# Power_Management.net
KiCad netlist of a schematic drawn in Altium Designer
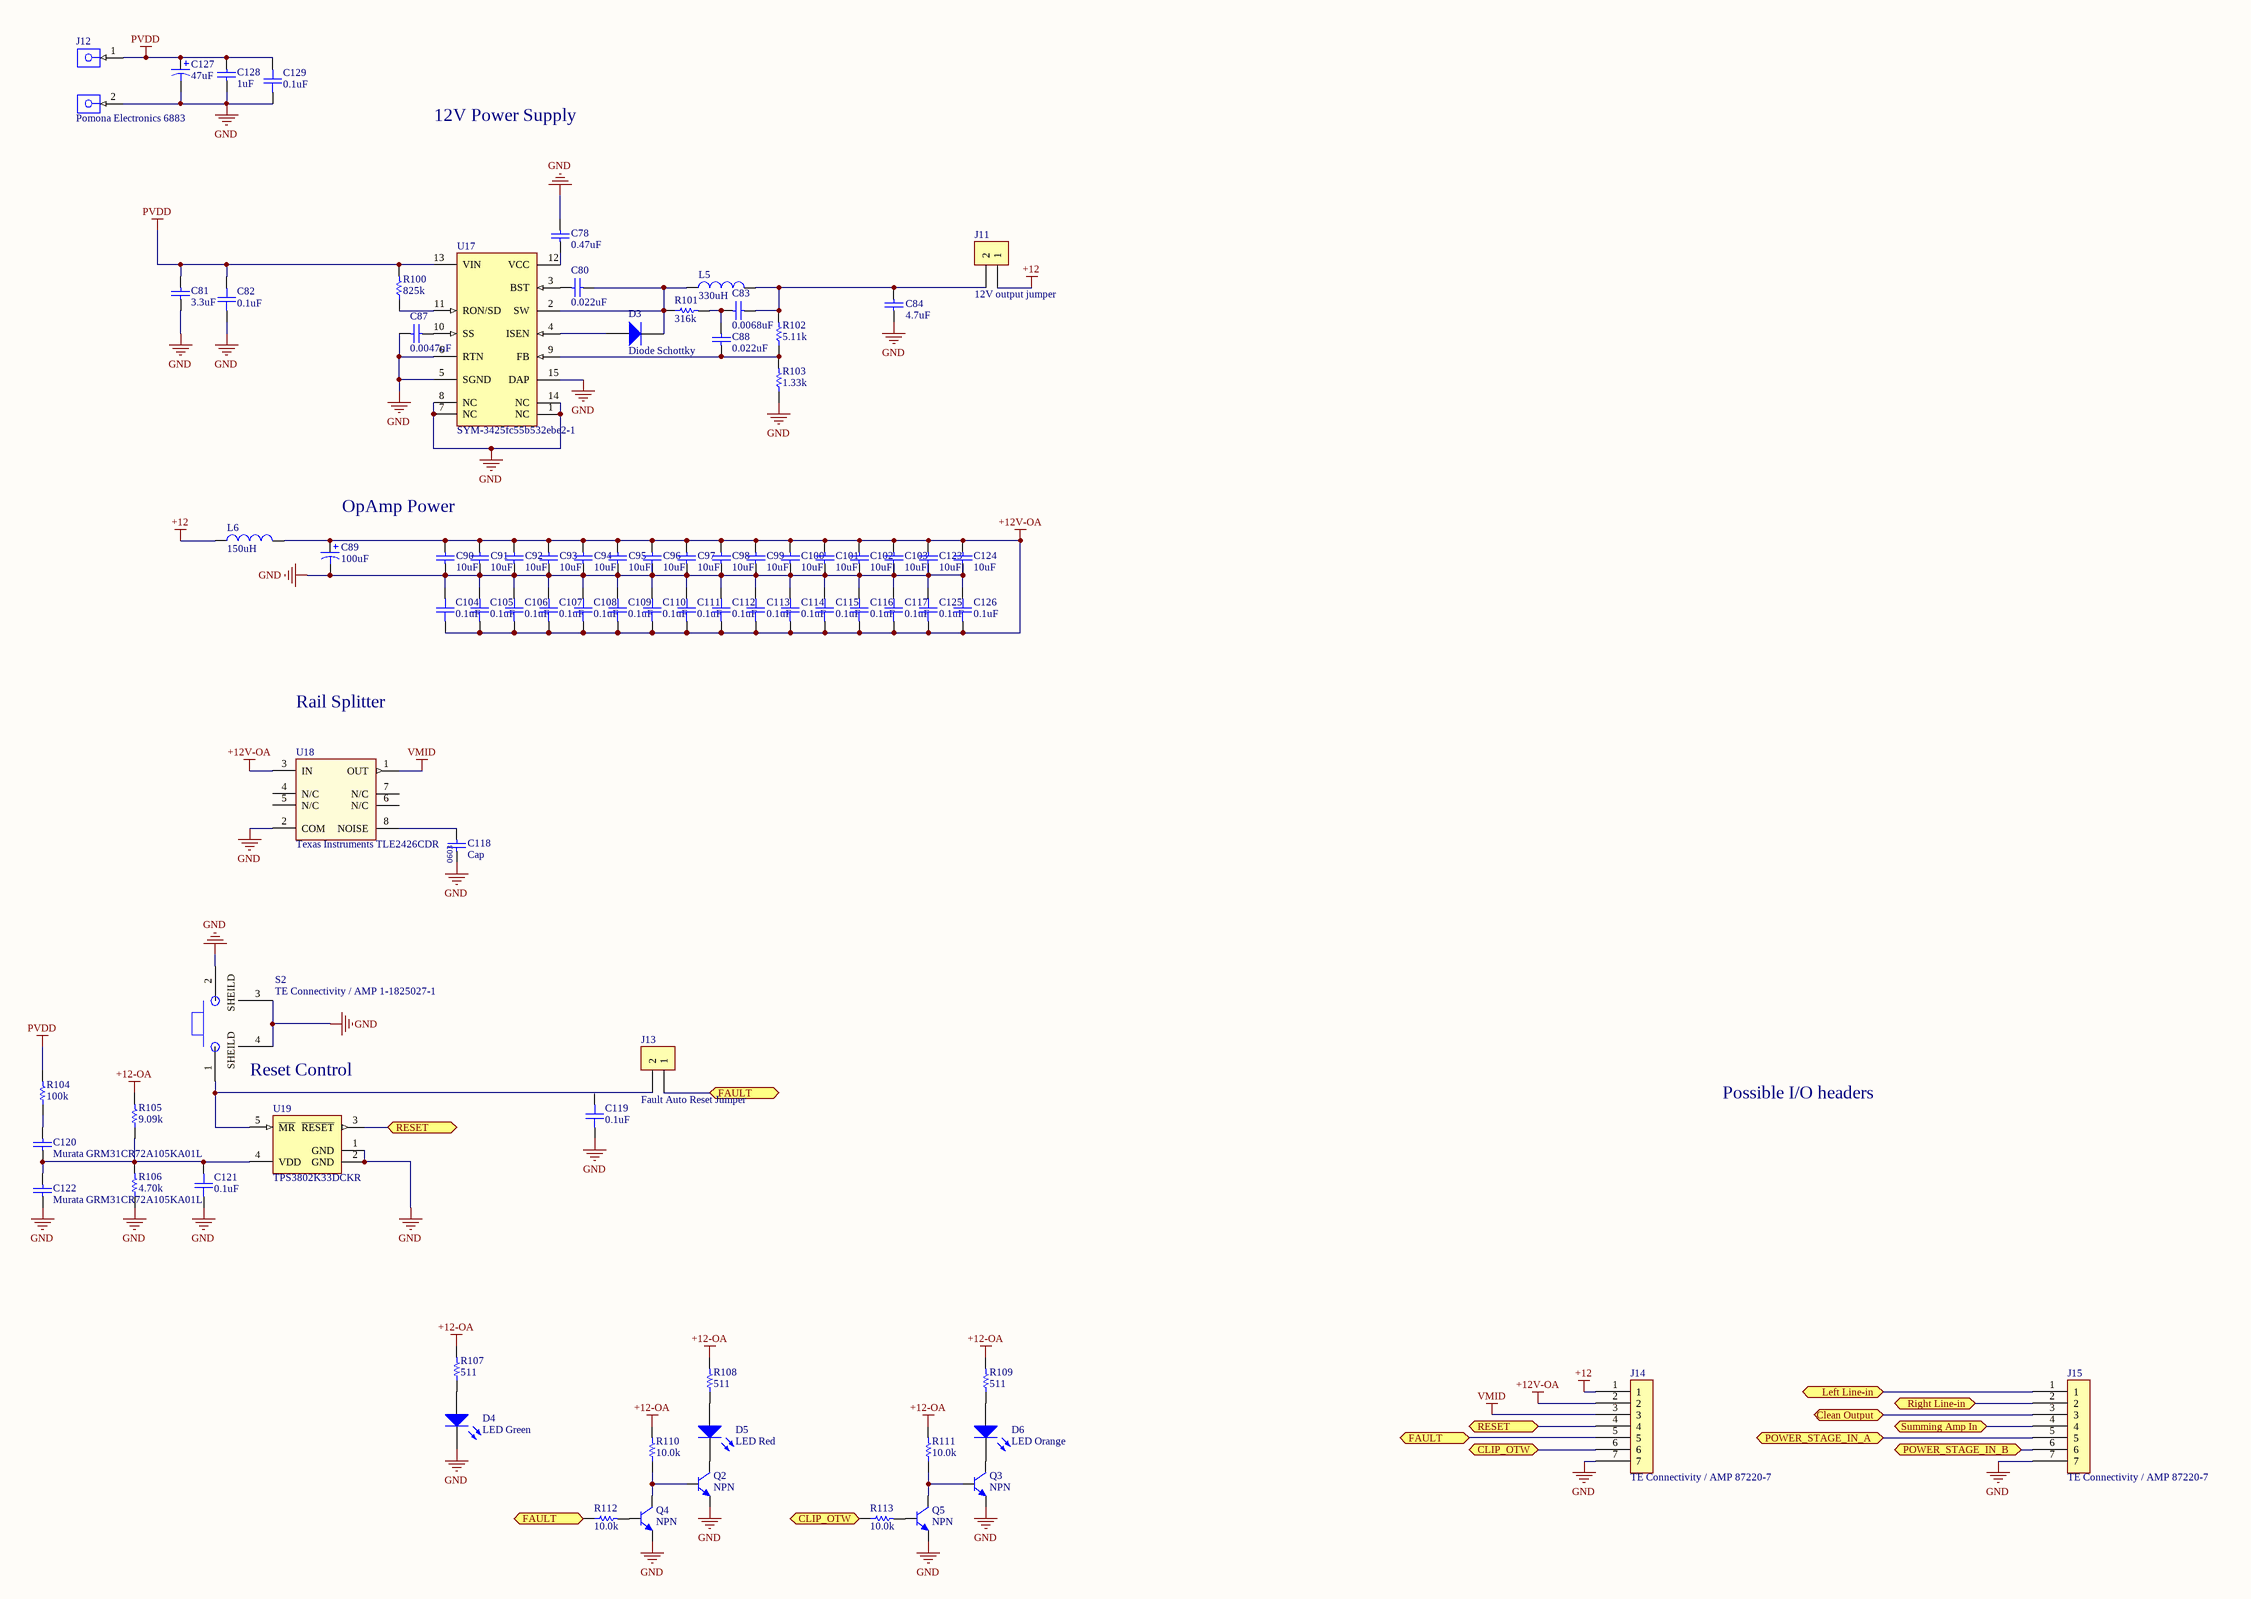
[diagram p0: Power Management.SchDoc]

(export (version "E")
  (design (tool "Eeschema 10.0.6"))
  (components
    (comp (ref "C78")
      (value "0.47uF")
      (footprint "PCB-i0dme2so6deleduh8uuv-1")
      (description "1206 0.47 uF 100 V ±10% Tolerance X7R Multilayer Ceramic Chip Capacitor")
      (fields (field (name "MANUFACTURER PART NUMBER") "CC1206KKX7R0BB474"))
      (libsource (lib "CommunityVault") (part "CMP-fe3b3644688f21fc-1"))
    )
    (comp (ref "C80")
      (value "0.022uF")
      (footprint "CAPC1608X87X35NL15T15")
      (description "CAP CER 0.022UF 100V X7R 0603")
      (fields
        (field (name "MANUFACTURER") "Kemet")
        (field (name "MANUFACTURER PART NUMBER") "C0603C223K1RACTU")
      )
      (libsource (lib "CommunityVault") (part "CMP-124409-3"))
    )
    (comp (ref "C81")
      (value "3.3uF")
      (footprint "PCB-chn8p1js4k1ngrwxbp4y-1")
      (description "Cap Ceramic 3.3uF 100V X7R 10% Pad SMD 1812 125C Automotive T/R")
      (fields (field (name "MANUFACTURER PART NUMBER") "C1812C335K1RACAUTO"))
      (libsource (lib "CommunityVault") (part "CMP-d69b1be3b579095c-1"))
    )
    (comp (ref "C82")
      (value "0.1uF")
      (footprint "PCB-jzhgzaa3ohr19x5vw660-1")
      (description "Capacitor 0.1 uF 100 Volt X7R 10% Surface Mount 0603 Paper Tape and Reel")
      (fields (field (name "MANUFACTURER PART NUMBER") "GRM188R72A104KA35D"))
      (libsource (lib "CommunityVault") (part "CMP-120189-6"))
    )
    (comp (ref "C83")
      (value "0.0068uF")
      (footprint "CAPC1608X06N")
      (description "Cap Ceramic 0.0068uF 100V C0G 5% Pad SMD 0603 125C T/R")
      (libsource (lib "CommunityVault") (part "CMP-2021ea3b622bffe6-1"))
    )
    (comp (ref "C84")
      (value "4.7uF")
      (footprint "CAPC2013X94X50LL20T25")
      (description "0805 4.7 uF 25 V ±20% Tolerance X5R SMT Multilayer Ceramic Capacitor")
      (fields
        (field (name "MANUFACTURER") "Murata")
        (field (name "MANUFACTURER PART NUMBER") "GRM21BR61E475MA12L")
      )
      (libsource (lib "CommunityVault") (part "CMP-120945-5"))
    )
    (comp (ref "C87")
      (value "0.0047uF")
      (footprint "CAPC2012X08M")
      (description "Cap Ceramic 0.0047uF 100V X7R 10% SMD 0805 125°C Paper T/R")
      (libsource (lib "CommunityVault") (part "CMP-1cbed49aa786c379-1"))
    )
    (comp (ref "C88")
      (value "0.022uF")
      (footprint "CAPC1608X87X35NL15T15")
      (description "CAP CER 0.022UF 100V X7R 0603")
      (fields
        (field (name "MANUFACTURER") "Kemet")
        (field (name "MANUFACTURER PART NUMBER") "C0603C223K1RACTU")
      )
      (libsource (lib "CommunityVault") (part "CMP-124409-3"))
    )
    (comp (ref "C89")
      (value "100uF")
      (footprint "PCB-in8pxjyymzgw21cvj8kw-1")
      (fields
        (field (name "MANUFACTURER PART NUMBER") "UCD1E101MCL1GS")
        (field (name "MANUFACTURER") "Nichicon")
      )
      (libsource (lib "CommunityVault") (part "CMP-0978c15ef0cfd6bf-1"))
    )
    (comp (ref "C90")
      (value "10uF")
      (footprint "CAPC3216X94X50NL20T25")
      (description "CL31 Series 10 uF 25 V ±10 % Tolerance X7R SMT Multilayer Ceramic Capacitor")
      (libsource (lib "CommunityVault") (part "SYM-a7396f2fa7ef78fe-1"))
    )
    (comp (ref "C91")
      (value "10uF")
      (footprint "CAPC3216X94X50NL20T25")
      (description "CL31 Series 10 uF 25 V ±10 % Tolerance X7R SMT Multilayer Ceramic Capacitor")
      (libsource (lib "CommunityVault") (part "SYM-a7396f2fa7ef78fe-1"))
    )
    (comp (ref "C92")
      (value "10uF")
      (footprint "CAPC3216X94X50NL20T25")
      (description "CL31 Series 10 uF 25 V ±10 % Tolerance X7R SMT Multilayer Ceramic Capacitor")
      (libsource (lib "CommunityVault") (part "SYM-a7396f2fa7ef78fe-1"))
    )
    (comp (ref "C93")
      (value "10uF")
      (footprint "CAPC3216X94X50NL20T25")
      (description "CL31 Series 10 uF 25 V ±10 % Tolerance X7R SMT Multilayer Ceramic Capacitor")
      (libsource (lib "CommunityVault") (part "SYM-a7396f2fa7ef78fe-1"))
    )
    (comp (ref "C94")
      (value "10uF")
      (footprint "CAPC3216X94X50NL20T25")
      (description "CL31 Series 10 uF 25 V ±10 % Tolerance X7R SMT Multilayer Ceramic Capacitor")
      (libsource (lib "CommunityVault") (part "SYM-a7396f2fa7ef78fe-1"))
    )
    (comp (ref "C95")
      (value "10uF")
      (footprint "CAPC3216X94X50NL20T25")
      (description "CL31 Series 10 uF 25 V ±10 % Tolerance X7R SMT Multilayer Ceramic Capacitor")
      (libsource (lib "CommunityVault") (part "SYM-a7396f2fa7ef78fe-1"))
    )
    (comp (ref "C96")
      (value "10uF")
      (footprint "CAPC3216X94X50NL20T25")
      (description "CL31 Series 10 uF 25 V ±10 % Tolerance X7R SMT Multilayer Ceramic Capacitor")
      (libsource (lib "CommunityVault") (part "SYM-a7396f2fa7ef78fe-1"))
    )
    (comp (ref "C97")
      (value "10uF")
      (footprint "CAPC3216X94X50NL20T25")
      (description "CL31 Series 10 uF 25 V ±10 % Tolerance X7R SMT Multilayer Ceramic Capacitor")
      (libsource (lib "CommunityVault") (part "SYM-a7396f2fa7ef78fe-1"))
    )
    (comp (ref "C98")
      (value "10uF")
      (footprint "CAPC3216X94X50NL20T25")
      (description "CL31 Series 10 uF 25 V ±10 % Tolerance X7R SMT Multilayer Ceramic Capacitor")
      (libsource (lib "CommunityVault") (part "SYM-a7396f2fa7ef78fe-1"))
    )
    (comp (ref "C99")
      (value "10uF")
      (footprint "CAPC3216X94X50NL20T25")
      (description "CL31 Series 10 uF 25 V ±10 % Tolerance X7R SMT Multilayer Ceramic Capacitor")
      (libsource (lib "CommunityVault") (part "SYM-a7396f2fa7ef78fe-1"))
    )
    (comp (ref "C100")
      (value "10uF")
      (footprint "CAPC3216X94X50NL20T25")
      (description "CL31 Series 10 uF 25 V ±10 % Tolerance X7R SMT Multilayer Ceramic Capacitor")
      (libsource (lib "CommunityVault") (part "SYM-a7396f2fa7ef78fe-1"))
    )
    (comp (ref "C101")
      (value "10uF")
      (footprint "CAPC3216X94X50NL20T25")
      (description "CL31 Series 10 uF 25 V ±10 % Tolerance X7R SMT Multilayer Ceramic Capacitor")
      (libsource (lib "CommunityVault") (part "SYM-a7396f2fa7ef78fe-1"))
    )
    (comp (ref "C102")
      (value "10uF")
      (footprint "CAPC3216X94X50NL20T25")
      (description "CL31 Series 10 uF 25 V ±10 % Tolerance X7R SMT Multilayer Ceramic Capacitor")
      (libsource (lib "CommunityVault") (part "SYM-a7396f2fa7ef78fe-1"))
    )
    (comp (ref "C103")
      (value "10uF")
      (footprint "CAPC3216X94X50NL20T25")
      (description "CL31 Series 10 uF 25 V ±10 % Tolerance X7R SMT Multilayer Ceramic Capacitor")
      (libsource (lib "CommunityVault") (part "SYM-a7396f2fa7ef78fe-1"))
    )
    (comp (ref "C104")
      (value "0.1uF")
      (footprint "PCB-jzhgzaa3ohr19x5vw660-1")
      (description "Capacitor 0.1 uF 100 Volt X7R 10% Surface Mount 0603 Paper Tape and Reel")
      (fields (field (name "MANUFACTURER PART NUMBER") "GRM188R72A104KA35D"))
      (libsource (lib "CommunityVault") (part "SYM-f4783d71d0362bbf-1"))
    )
    (comp (ref "C105")
      (value "0.1uF")
      (footprint "PCB-jzhgzaa3ohr19x5vw660-1")
      (description "Capacitor 0.1 uF 100 Volt X7R 10% Surface Mount 0603 Paper Tape and Reel")
      (fields (field (name "MANUFACTURER PART NUMBER") "GRM188R72A104KA35D"))
      (libsource (lib "CommunityVault") (part "SYM-f4783d71d0362bbf-1"))
    )
    (comp (ref "C106")
      (value "0.1uF")
      (footprint "PCB-jzhgzaa3ohr19x5vw660-1")
      (description "Capacitor 0.1 uF 100 Volt X7R 10% Surface Mount 0603 Paper Tape and Reel")
      (fields (field (name "MANUFACTURER PART NUMBER") "GRM188R72A104KA35D"))
      (libsource (lib "CommunityVault") (part "SYM-f4783d71d0362bbf-1"))
    )
    (comp (ref "C107")
      (value "0.1uF")
      (footprint "PCB-jzhgzaa3ohr19x5vw660-1")
      (description "Capacitor 0.1 uF 100 Volt X7R 10% Surface Mount 0603 Paper Tape and Reel")
      (fields (field (name "MANUFACTURER PART NUMBER") "GRM188R72A104KA35D"))
      (libsource (lib "CommunityVault") (part "SYM-f4783d71d0362bbf-1"))
    )
    (comp (ref "C108")
      (value "0.1uF")
      (footprint "PCB-jzhgzaa3ohr19x5vw660-1")
      (description "Capacitor 0.1 uF 100 Volt X7R 10% Surface Mount 0603 Paper Tape and Reel")
      (fields (field (name "MANUFACTURER PART NUMBER") "GRM188R72A104KA35D"))
      (libsource (lib "CommunityVault") (part "SYM-f4783d71d0362bbf-1"))
    )
    (comp (ref "C109")
      (value "0.1uF")
      (footprint "PCB-jzhgzaa3ohr19x5vw660-1")
      (description "Capacitor 0.1 uF 100 Volt X7R 10% Surface Mount 0603 Paper Tape and Reel")
      (fields (field (name "MANUFACTURER PART NUMBER") "GRM188R72A104KA35D"))
      (libsource (lib "CommunityVault") (part "SYM-f4783d71d0362bbf-1"))
    )
    (comp (ref "C110")
      (value "0.1uF")
      (footprint "PCB-jzhgzaa3ohr19x5vw660-1")
      (description "Capacitor 0.1 uF 100 Volt X7R 10% Surface Mount 0603 Paper Tape and Reel")
      (fields (field (name "MANUFACTURER PART NUMBER") "GRM188R72A104KA35D"))
      (libsource (lib "CommunityVault") (part "SYM-f4783d71d0362bbf-1"))
    )
    (comp (ref "C111")
      (value "0.1uF")
      (footprint "PCB-jzhgzaa3ohr19x5vw660-1")
      (description "Capacitor 0.1 uF 100 Volt X7R 10% Surface Mount 0603 Paper Tape and Reel")
      (fields (field (name "MANUFACTURER PART NUMBER") "GRM188R72A104KA35D"))
      (libsource (lib "CommunityVault") (part "SYM-f4783d71d0362bbf-1"))
    )
    (comp (ref "C112")
      (value "0.1uF")
      (footprint "PCB-jzhgzaa3ohr19x5vw660-1")
      (description "Capacitor 0.1 uF 100 Volt X7R 10% Surface Mount 0603 Paper Tape and Reel")
      (fields (field (name "MANUFACTURER PART NUMBER") "GRM188R72A104KA35D"))
      (libsource (lib "CommunityVault") (part "SYM-f4783d71d0362bbf-1"))
    )
    (comp (ref "C113")
      (value "0.1uF")
      (footprint "PCB-jzhgzaa3ohr19x5vw660-1")
      (description "Capacitor 0.1 uF 100 Volt X7R 10% Surface Mount 0603 Paper Tape and Reel")
      (fields (field (name "MANUFACTURER PART NUMBER") "GRM188R72A104KA35D"))
      (libsource (lib "CommunityVault") (part "SYM-f4783d71d0362bbf-1"))
    )
    (comp (ref "C114")
      (value "0.1uF")
      (footprint "PCB-jzhgzaa3ohr19x5vw660-1")
      (description "Capacitor 0.1 uF 100 Volt X7R 10% Surface Mount 0603 Paper Tape and Reel")
      (fields (field (name "MANUFACTURER PART NUMBER") "GRM188R72A104KA35D"))
      (libsource (lib "CommunityVault") (part "SYM-f4783d71d0362bbf-1"))
    )
    (comp (ref "C115")
      (value "0.1uF")
      (footprint "PCB-jzhgzaa3ohr19x5vw660-1")
      (description "Capacitor 0.1 uF 100 Volt X7R 10% Surface Mount 0603 Paper Tape and Reel")
      (fields (field (name "MANUFACTURER PART NUMBER") "GRM188R72A104KA35D"))
      (libsource (lib "CommunityVault") (part "SYM-f4783d71d0362bbf-1"))
    )
    (comp (ref "C116")
      (value "0.1uF")
      (footprint "PCB-jzhgzaa3ohr19x5vw660-1")
      (description "Capacitor 0.1 uF 100 Volt X7R 10% Surface Mount 0603 Paper Tape and Reel")
      (fields (field (name "MANUFACTURER PART NUMBER") "GRM188R72A104KA35D"))
      (libsource (lib "CommunityVault") (part "SYM-f4783d71d0362bbf-1"))
    )
    (comp (ref "C117")
      (value "0.1uF")
      (footprint "PCB-jzhgzaa3ohr19x5vw660-1")
      (description "Capacitor 0.1 uF 100 Volt X7R 10% Surface Mount 0603 Paper Tape and Reel")
      (fields (field (name "MANUFACTURER PART NUMBER") "GRM188R72A104KA35D"))
      (libsource (lib "CommunityVault") (part "SYM-f4783d71d0362bbf-1"))
    )
    (comp (ref "C118")
      (value "Cap")
      (footprint "CAPC1608X07N")
      (description "0603 1 uF 16V ±10% Tolerance X7R SMT Multilayer Ceramic Capacitor")
      (fields (field (name "MANUFACTURER PART NUMBER") "GRM188R71C105KE15D"))
      (libsource (lib "CommunityVault") (part "SYM-463c8d25af8a99fb-1"))
    )
    (comp (ref "C119")
      (value "0.1uF")
      (footprint "PCB-jzhgzaa3ohr19x5vw660-1")
      (description "Capacitor 0.1 uF 100 Volt X7R 10% Surface Mount 0603 Paper Tape and Reel")
      (fields (field (name "MANUFACTURER PART NUMBER") "GRM188R72A104KA35D"))
      (libsource (lib "CommunityVault") (part "CMP-120189-6"))
    )
    (comp (ref "C120")
      (value "Murata GRM31CR72A105KA01L")
      (footprint "CAPC3216X180X55NL20T25")
      (description "CAP CER 1UF 100V 10% X7R 1206")
      (libsource (lib "CommunityVault") (part "CMP-19299756-2"))
    )
    (comp (ref "C121")
      (value "0.1uF")
      (footprint "PCB-jzhgzaa3ohr19x5vw660-1")
      (description "Capacitor 0.1 uF 100 Volt X7R 10% Surface Mount 0603 Paper Tape and Reel")
      (fields (field (name "MANUFACTURER PART NUMBER") "GRM188R72A104KA35D"))
      (libsource (lib "CommunityVault") (part "CMP-120189-6"))
    )
    (comp (ref "C122")
      (value "Murata GRM31CR72A105KA01L")
      (footprint "CAPC3216X180X55NL20T25")
      (description "CAP CER 1UF 100V 10% X7R 1206")
      (libsource (lib "CommunityVault") (part "CMP-19299756-2"))
    )
    (comp (ref "C123")
      (value "10uF")
      (footprint "CAPC3216X94X50NL20T25")
      (description "CL31 Series 10 uF 25 V ±10 % Tolerance X7R SMT Multilayer Ceramic Capacitor")
      (libsource (lib "CommunityVault") (part "CMP-a7396f2fa7ef78fe-6"))
    )
    (comp (ref "C124")
      (value "10uF")
      (footprint "CAPC3216X94X50NL20T25")
      (description "CL31 Series 10 uF 25 V ±10 % Tolerance X7R SMT Multilayer Ceramic Capacitor")
      (libsource (lib "CommunityVault") (part "CMP-a7396f2fa7ef78fe-6"))
    )
    (comp (ref "C125")
      (value "0.1uF")
      (footprint "PCB-jzhgzaa3ohr19x5vw660-1")
      (description "Capacitor 0.1 uF 100 Volt X7R 10% Surface Mount 0603 Paper Tape and Reel")
      (fields (field (name "MANUFACTURER PART NUMBER") "GRM188R72A104KA35D"))
      (libsource (lib "CommunityVault") (part "CMP-120189-6"))
    )
    (comp (ref "C126")
      (value "0.1uF")
      (footprint "PCB-jzhgzaa3ohr19x5vw660-1")
      (description "Capacitor 0.1 uF 100 Volt X7R 10% Surface Mount 0603 Paper Tape and Reel")
      (fields (field (name "MANUFACTURER PART NUMBER") "GRM188R72A104KA35D"))
      (libsource (lib "CommunityVault") (part "CMP-120189-6"))
    )
    (comp (ref "C127")
      (value "47uF")
      (footprint "PCBComponent_1")
      (description "Cap Aluminum Lytic 47uF 100V 20% (10 X 10.2mm) SMD 170mA 2000h 105C T/R")
      (libsource (lib "CommunityVault") (part "SYM-6614abbd7d9eb9d3-1"))
    )
    (comp (ref "C128")
      (value "1uF")
      (footprint "CAPC3216X180X55NL20T25")
      (description "CAP CER 1UF 100V 10% X7R 1206")
      (fields
        (field (name "MANUFACTURER") "Murata")
        (field (name "MANUFACTURER PART NUMBER") "GRM31CR72A105KA01L")
      )
      (libsource (lib "CommunityVault") (part "CMP-19299756-2"))
    )
    (comp (ref "C129")
      (value "0.1uF")
      (footprint "PCB-jzhgzaa3ohr19x5vw660-1")
      (description "Capacitor 0.1 uF 100 Volt X7R 10% Surface Mount 0603 Paper Tape and Reel")
      (fields (field (name "MANUFACTURER PART NUMBER") "GRM188R72A104KA35D"))
      (libsource (lib "CommunityVault") (part "CMP-120189-6"))
    )
    (comp (ref "D3")
      (value "Diode Schottky")
      (footprint "PCB-iur9xjol2nuz7see6iaw-1")
      (description "10 Amp 150V Ultra-Low VF schottky rectifier / TAPE REEL")
      (fields
        (field (name "MANUFACTURER PART NUMBER") "FSV10150V")
        (field (name "MANUFACTURER") "ON Semiconductor")
      )
      (libsource (lib "CommunityVault") (part "CMP-3c2bf027d984e3ec-1"))
    )
    (comp (ref "D4")
      (value "LED Green")
      (footprint "PCB - LS A67K")
      (description "Green 1.6 x 0.6 x 1.15 mm 130° Water Clear 18 to 78 mcd 2 V SMT LED")
      (fields
        (field (name "MANUFACTURER") "Lite-On")
        (field (name "MANUFACTURER PART NUMBER") "LTST-S270KGKT")
      )
      (libsource (lib "CommunityVault") (part "SYM-1022331-1"))
    )
    (comp (ref "D5")
      (value "LED Red")
      (footprint "PCB - LS A67K")
      (description "LED; SMD; 0604; red; 18-54mcd; 1.6x1.15x0.6mm; 130°; 2÷2.4V; 20mA")
      (fields
        (field (name "MANUFACTURER PART NUMBER") "LTST-S270KRKT")
        (field (name "MANUFACTURER") "Lite-On")
      )
      (libsource (lib "CommunityVault") (part "CMP-1417dd155542cbd0-5"))
    )
    (comp (ref "D6")
      (value "LED Orange")
      (footprint "PCB - LS A67K")
      (description "Orange 1.6 x 0.6 mm 130º 90 mcd 2 V Water Clear Surface Mount Chip LED")
      (fields
        (field (name "MANUFACTURER PART NUMBER") "LTST-S270KFKT")
        (field (name "MANUFACTURER") "Lite-On")
      )
      (libsource (lib "CommunityVault") (part "CMP-31d7f8d570b5ee10-2"))
    )
    (comp (ref "J11")
      (value "12V output jumper")
      (footprint "PCB-atpiihg40e8c2nmcy2an-1")
      (description "Connector Unshrouded Header 2 Position 2.54mm Solder Straight Thru-Hole")
      (libsource (lib "CommunityVault") (part "CMP-2792ecc2f21af855-16"))
    )
    (comp (ref "J12")
      (value "Pomona Electronics 6883")
      (footprint "PCB-19368571-1")
      (description "DUAL BINDING POSTS")
      (libsource (lib "CommunityVault") (part "SYM-19368571-1"))
    )
    (comp (ref "J13")
      (value "Fault Auto Reset Jumper")
      (footprint "PCB-atpiihg40e8c2nmcy2an-1")
      (description "Connector Unshrouded Header 2 Position 2.54mm Solder Straight Thru-Hole")
      (libsource (lib "CommunityVault") (part "CMP-2792ecc2f21af855-16"))
    )
    (comp (ref "J14")
      (value "TE Connectivity / AMP 87220-7")
      (footprint "PCB-2nimx3srux7q5lcqcrab-1")
      (description "AMPMODU 7 Position Through-Hole Single Row Straight 0.1 Inch Header")
      (fields (field (name "MANUFACTURER PART NUMBER") "87220-7"))
      (libsource (lib "CommunityVault") (part "CMP-ebeb20bb2956342c-1"))
    )
    (comp (ref "J15")
      (value "TE Connectivity / AMP 87220-7")
      (footprint "PCB-2nimx3srux7q5lcqcrab-1")
      (description "AMPMODU 7 Position Through-Hole Single Row Straight 0.1 Inch Header")
      (fields (field (name "MANUFACTURER PART NUMBER") "87220-7"))
      (libsource (lib "CommunityVault") (part "CMP-ebeb20bb2956342c-1"))
    )
    (comp (ref "L5")
      (value "330uH")
      (footprint "Coilcraft MSS1210")
      (description "Power inductor, shielded, 10/20% tol, SMT, RoHS")
      (libsource (lib "CommunityVault") (part "CMP-f7073f765ac228c0-1"))
    )
    (comp (ref "L6")
      (value "150uH")
      (footprint "PCB-lfrzme2idivti55vz3sm-1")
      (description "SLF Series 12.5 x 12.5 mm 150 uH ±20 % Tol. 1.5 A Shielded SMT Power Inductor")
      (fields
        (field (name "MANUFACTURER PART NUMBER") "SLF12575T-151M1R5-PF")
        (field (name "MANUFACTURER") "TDK")
      )
      (libsource (lib "CommunityVault") (part "CMP-1963d06f268dc6a4-1"))
    )
    (comp (ref "Q2")
      (value "NPN")
      (footprint "PCB-zwf9crilb66v8jey4z70-1")
      (description "Bipolar (BJT) Single Transistor, General Purpose, NPN, 40 V, 300 MHz, 225 mW, 600 mA, 300")
      (libsource (lib "CommunityVault") (part "SYM-db1c115bb65504db-1"))
    )
    (comp (ref "Q3")
      (value "NPN")
      (footprint "PCB-zwf9crilb66v8jey4z70-1")
      (description "Bipolar (BJT) Single Transistor, General Purpose, NPN, 40 V, 300 MHz, 225 mW, 600 mA, 300")
      (libsource (lib "CommunityVault") (part "SYM-db1c115bb65504db-1"))
    )
    (comp (ref "Q4")
      (value "NPN")
      (footprint "PCB-zwf9crilb66v8jey4z70-1")
      (description "Bipolar (BJT) Single Transistor, General Purpose, NPN, 40 V, 300 MHz, 225 mW, 600 mA, 300")
      (libsource (lib "CommunityVault") (part "SYM-db1c115bb65504db-1"))
    )
    (comp (ref "Q5")
      (value "NPN")
      (footprint "PCB-zwf9crilb66v8jey4z70-1")
      (description "Bipolar (BJT) Single Transistor, General Purpose, NPN, 40 V, 300 MHz, 225 mW, 600 mA, 300")
      (libsource (lib "CommunityVault") (part "SYM-db1c115bb65504db-1"))
    )
    (comp (ref "R100")
      (value "825k")
      (footprint "RESC1609X55X28LL05T18")
      (description "Res Thin Film 0603 825K Ohm 1% 1/10W ±50ppm/°C Molded SMD SMD Paper T/R")
      (libsource (lib "CommunityVault") (part "CMP-1319d8bf3abaccde-1"))
    )
    (comp (ref "R101")
      (value "316k")
      (footprint "RESC1609X55X28LL05T18")
      (description "Surface Mount Thin Film Resistor, MCT Series, 316 kohm, 100 mW, - 0.1%, 75 V")
      (fields
        (field (name "MANUFACTURER") "Vishay")
        (field (name "MANUFACTURER PART NUMBER") "MCT06030E3163BP100")
      )
      (libsource (lib "CommunityVault") (part "CMP-8e64436f049d51a3-1"))
    )
    (comp (ref "R102")
      (value "5.11k")
      (footprint "PCB-dm6f2vlmfnf97yy2nsh5-1")
      (description "Res Thin Film 0603 5.11K Ohm 0.1% 1/10W ±25ppm/°C Molded SMD SMD Paper T/R")
      (fields (field (name "MANUFACTURER PART NUMBER") "MCT06030D5111BP100"))
      (libsource (lib "CommunityVault") (part "CMP-3220f9ecb51bede7-1"))
    )
    (comp (ref "R103")
      (value "1.33k")
      (footprint "RESC1609X55X28LL05T18")
      (description "Res Thnflm 0603 1.33k Ohm 0.1% 1/10w 25ppm/ c Smd")
      (libsource (lib "CommunityVault") (part "CMP-aade615395077519-1"))
    )
    (comp (ref "R104")
      (value "100k")
      (footprint "RESC1609X55X28LL05T18")
      (description "MCT Series 0603 0.125 W 100 kOhm ±0.1% ±25 ppm/K SMT Thin Film Chip Resistor")
      (fields (field (name "MANUFACTURER") "Vishay"))
      (libsource (lib "CommunityVault") (part "SYM-b20e79a018766dc9-1"))
    )
    (comp (ref "R105")
      (value "9.09k")
      (footprint "RESC1609X55X28LL05T18")
      (description "Res Smd 9.09k Ohm 0.1% 1/8w 0603")
      (fields
        (field (name "MANUFACTURER") "Vishay")
        (field (name "MANUFACTURER PART NUMBER") "MCT0603MD9091BP100")
      )
      (libsource (lib "CommunityVault") (part "SYM-504998d4ca0f8f8e-1"))
    )
    (comp (ref "R106")
      (value "4.70k")
      (footprint "RESC1609X55X28LL05T18")
      (description "Surface Mount Chip Resistor, Thin Film, MCT Series, 4.7 kohm, 125 mW, 0.1%, 75 V")
      (libsource (lib "CommunityVault") (part "SYM-2ab0e11e80e8f577-1"))
    )
    (comp (ref "R107")
      (value "511")
      (footprint "RESC1609X55X28LL05T18")
      (description "Res Thin Film 0603 511 Ohm 0.1% 1/10W ±25ppm/°C Molded SMD SMD Paper T/R")
      (libsource (lib "CommunityVault") (part "SYM-7c87b70a42aea340-1"))
    )
    (comp (ref "R108")
      (value "511")
      (footprint "RESC1609X55X28LL05T18")
      (description "Res Thin Film 0603 511 Ohm 0.1% 1/10W ±25ppm/°C Molded SMD SMD Paper T/R")
      (libsource (lib "CommunityVault") (part "SYM-7c87b70a42aea340-1"))
    )
    (comp (ref "R109")
      (value "511")
      (footprint "RESC1609X55X28LL05T18")
      (description "Res Thin Film 0603 511 Ohm 0.1% 1/10W ±25ppm/°C Molded SMD SMD Paper T/R")
      (libsource (lib "CommunityVault") (part "SYM-7c87b70a42aea340-1"))
    )
    (comp (ref "R110")
      (value "10.0k")
      (footprint "RESC1609X55X28LL05T18")
      (description "Precision Thin Film Smnt Resistor 0603 Case 10kOhm +/-0.1% 0.1W +/-25ppm/degC")
      (fields
        (field (name "MANUFACTURER") "Vishay")
        (field (name "MANUFACTURER PART NUMBER") "MCT06030D1002BP100")
      )
      (libsource (lib "CommunityVault") (part "SYM-893e42b9f3a056f9-1"))
    )
    (comp (ref "R111")
      (value "10.0k")
      (footprint "RESC1609X55X28LL05T18")
      (description "Precision Thin Film Smnt Resistor 0603 Case 10kOhm +/-0.1% 0.1W +/-25ppm/degC")
      (fields
        (field (name "MANUFACTURER") "Vishay")
        (field (name "MANUFACTURER PART NUMBER") "MCT06030D1002BP100")
      )
      (libsource (lib "CommunityVault") (part "SYM-893e42b9f3a056f9-1"))
    )
    (comp (ref "R112")
      (value "10.0k")
      (footprint "RESC1609X55X28LL05T18")
      (description "Precision Thin Film Smnt Resistor 0603 Case 10kOhm +/-0.1% 0.1W +/-25ppm/degC")
      (fields
        (field (name "MANUFACTURER") "Vishay")
        (field (name "MANUFACTURER PART NUMBER") "MCT06030D1002BP100")
      )
      (libsource (lib "CommunityVault") (part "SYM-893e42b9f3a056f9-1"))
    )
    (comp (ref "R113")
      (value "10.0k")
      (footprint "RESC1609X55X28LL05T18")
      (description "Precision Thin Film Smnt Resistor 0603 Case 10kOhm +/-0.1% 0.1W +/-25ppm/degC")
      (fields
        (field (name "MANUFACTURER") "Vishay")
        (field (name "MANUFACTURER PART NUMBER") "MCT06030D1002BP100")
      )
      (libsource (lib "CommunityVault") (part "SYM-893e42b9f3a056f9-1"))
    )
    (comp (ref "S2")
      (value "TE Connectivity / AMP 1-1825027-1")
      (footprint "PCB-z0tn1x4l8qb5b43a6q2n-1")
      (description "Switch Push Button OFF (ON) SPST Round Button 0.05A 24VDC Momentary Contact PC Pins Thru-Hole")
      (libsource (lib "CommunityVault") (part "CMP-4d86860896969241-7"))
    )
    (comp (ref "U17")
      (value "SYM-3425fc55b532ebe2-1")
      (footprint "PCB-d66e4jgxn3exdfjea6yc-1")
      (description "8-75V Wide Vin, 1A Constant On-Time Non-Synchronous Buck egulator 14-HTSSOP -40 to 125")
      (fields (field (name "MANUFACTURER PART NUMBER") "LM5010MHX/NOPB"))
      (libsource (lib "CommunityVault") (part "SYM-3425fc55b532ebe2-1"))
    )
    (comp (ref "U18")
      (value "Texas Instruments TLE2426CDR")
      (footprint "INF-PG-DSO-8-3_M")
      (description "The ' ail Splitter' Precision Virtual Ground 8-SOIC")
      (fields (field (name "MANUFACTURER PART NUMBER") "TLE2426CDG4") (field (name "MANUFACTURER") "TI"))
      (libsource (lib "CommunityVault") (part "CMP-84004d2919695bc7-1"))
    )
    (comp (ref "U19")
      (value "TPS3802K33DCKR")
      (footprint "DCK5_N")
      (libsource (lib "CommunityVault") (part "CMP-4881249-2"))
    )
  )
  (nets
    (net (code "1") (name "+12") (class "Default")
      (node (ref "J11") (pin "1") (pinfunction "1_1") (pintype "power_in"))
      (node (ref "J14") (pin "1") (pinfunction "1_1") (pintype "passive"))
      (node (ref "L6") (pin "1") (pinfunction "1_1") (pintype "passive"))
    )
    (net (code "2") (name "+12-OA") (class "Default")
      (node (ref "R105") (pin "2") (pinfunction "2_2") (pintype "passive"))
      (node (ref "R107") (pin "2") (pinfunction "2_2") (pintype "passive"))
      (node (ref "R108") (pin "2") (pinfunction "2_2") (pintype "passive"))
      (node (ref "R109") (pin "2") (pinfunction "2_2") (pintype "passive"))
      (node (ref "R110") (pin "2") (pinfunction "2_2") (pintype "passive"))
      (node (ref "R111") (pin "2") (pinfunction "2_2") (pintype "passive"))
    )
    (net (code "3") (name "+12V-OA") (class "Default")
      (node (ref "C100") (pin "2") (pinfunction "2_2") (pintype "passive"))
      (node (ref "C101") (pin "2") (pinfunction "2_2") (pintype "passive"))
      (node (ref "C102") (pin "2") (pinfunction "2_2") (pintype "passive"))
      (node (ref "C103") (pin "2") (pinfunction "2_2") (pintype "passive"))
      (node (ref "C104") (pin "1") (pinfunction "1_1") (pintype "passive"))
      (node (ref "C105") (pin "1") (pinfunction "1_1") (pintype "passive"))
      (node (ref "C106") (pin "1") (pinfunction "1_1") (pintype "passive"))
      (node (ref "C107") (pin "1") (pinfunction "1_1") (pintype "passive"))
      (node (ref "C108") (pin "1") (pinfunction "1_1") (pintype "passive"))
      (node (ref "C109") (pin "1") (pinfunction "1_1") (pintype "passive"))
      (node (ref "C110") (pin "1") (pinfunction "1_1") (pintype "passive"))
      (node (ref "C111") (pin "1") (pinfunction "1_1") (pintype "passive"))
      (node (ref "C112") (pin "1") (pinfunction "1_1") (pintype "passive"))
      (node (ref "C113") (pin "1") (pinfunction "1_1") (pintype "passive"))
      (node (ref "C114") (pin "1") (pinfunction "1_1") (pintype "passive"))
      (node (ref "C115") (pin "1") (pinfunction "1_1") (pintype "passive"))
      (node (ref "C116") (pin "1") (pinfunction "1_1") (pintype "passive"))
      (node (ref "C117") (pin "1") (pinfunction "1_1") (pintype "passive"))
      (node (ref "C123") (pin "2") (pinfunction "2_2") (pintype "passive"))
      (node (ref "C124") (pin "2") (pinfunction "2_2") (pintype "passive"))
      (node (ref "C125") (pin "1") (pinfunction "1_1") (pintype "passive"))
      (node (ref "C126") (pin "1") (pinfunction "1_1") (pintype "passive"))
      (node (ref "C89") (pin "1") (pinfunction "1_1") (pintype "passive"))
      (node (ref "C90") (pin "2") (pinfunction "2_2") (pintype "passive"))
      (node (ref "C91") (pin "2") (pinfunction "2_2") (pintype "passive"))
      (node (ref "C92") (pin "2") (pinfunction "2_2") (pintype "passive"))
      (node (ref "C93") (pin "2") (pinfunction "2_2") (pintype "passive"))
      (node (ref "C94") (pin "2") (pinfunction "2_2") (pintype "passive"))
      (node (ref "C95") (pin "2") (pinfunction "2_2") (pintype "passive"))
      (node (ref "C96") (pin "2") (pinfunction "2_2") (pintype "passive"))
      (node (ref "C97") (pin "2") (pinfunction "2_2") (pintype "passive"))
      (node (ref "C98") (pin "2") (pinfunction "2_2") (pintype "passive"))
      (node (ref "C99") (pin "2") (pinfunction "2_2") (pintype "passive"))
      (node (ref "J14") (pin "2") (pinfunction "2_2") (pintype "passive"))
      (node (ref "L6") (pin "2") (pinfunction "2_2") (pintype "passive"))
      (node (ref "U18") (pin "3") (pinfunction "IN_3") (pintype "power_in"))
    )
    (net (code "4") (name "/CLIP_OTW") (class "Default")
      (node (ref "J14") (pin "6") (pinfunction "6_6") (pintype "passive"))
      (node (ref "R113") (pin "1") (pinfunction "1_1") (pintype "passive"))
    )
    (net (code "5") (name "/Clean Output") (class "Default")
      (node (ref "J15") (pin "3") (pinfunction "3_3") (pintype "passive"))
    )
    (net (code "6") (name "/FAULT") (class "Default")
      (node (ref "J13") (pin "1") (pinfunction "1_1") (pintype "power_in"))
      (node (ref "J14") (pin "5") (pinfunction "5_5") (pintype "passive"))
      (node (ref "R112") (pin "1") (pinfunction "1_1") (pintype "passive"))
    )
    (net (code "7") (name "/Left Line-in") (class "Default")
      (node (ref "J15") (pin "1") (pinfunction "1_1") (pintype "passive"))
    )
    (net (code "8") (name "/POWER_STAGE_IN_A") (class "Default")
      (node (ref "J15") (pin "5") (pinfunction "5_5") (pintype "passive"))
    )
    (net (code "9") (name "/POWER_STAGE_IN_B") (class "Default")
      (node (ref "J15") (pin "6") (pinfunction "6_6") (pintype "passive"))
    )
    (net (code "10") (name "/RESET") (class "Default")
      (node (ref "J14") (pin "4") (pinfunction "4_4") (pintype "passive"))
      (node (ref "U19") (pin "3") (pinfunction "~{RESET}_3") (pintype "output"))
    )
    (net (code "11") (name "/Right Line-in") (class "Default")
      (node (ref "J15") (pin "2") (pinfunction "2_2") (pintype "passive"))
    )
    (net (code "12") (name "/Summing Amp In") (class "Default")
      (node (ref "J15") (pin "4") (pinfunction "4_4") (pintype "passive"))
    )
    (net (code "13") (name "GND") (class "Default")
      (node (ref "C100") (pin "1") (pinfunction "1_1") (pintype "passive"))
      (node (ref "C101") (pin "1") (pinfunction "1_1") (pintype "passive"))
      (node (ref "C102") (pin "1") (pinfunction "1_1") (pintype "passive"))
      (node (ref "C103") (pin "1") (pinfunction "1_1") (pintype "passive"))
      (node (ref "C104") (pin "2") (pinfunction "2_2") (pintype "passive"))
      (node (ref "C105") (pin "2") (pinfunction "2_2") (pintype "passive"))
      (node (ref "C106") (pin "2") (pinfunction "2_2") (pintype "passive"))
      (node (ref "C107") (pin "2") (pinfunction "2_2") (pintype "passive"))
      (node (ref "C108") (pin "2") (pinfunction "2_2") (pintype "passive"))
      (node (ref "C109") (pin "2") (pinfunction "2_2") (pintype "passive"))
      (node (ref "C110") (pin "2") (pinfunction "2_2") (pintype "passive"))
      (node (ref "C111") (pin "2") (pinfunction "2_2") (pintype "passive"))
      (node (ref "C112") (pin "2") (pinfunction "2_2") (pintype "passive"))
      (node (ref "C113") (pin "2") (pinfunction "2_2") (pintype "passive"))
      (node (ref "C114") (pin "2") (pinfunction "2_2") (pintype "passive"))
      (node (ref "C115") (pin "2") (pinfunction "2_2") (pintype "passive"))
      (node (ref "C116") (pin "2") (pinfunction "2_2") (pintype "passive"))
      (node (ref "C117") (pin "2") (pinfunction "2_2") (pintype "passive"))
      (node (ref "C118") (pin "1") (pinfunction "1_1") (pintype "passive"))
      (node (ref "C119") (pin "1") (pinfunction "1_1") (pintype "passive"))
      (node (ref "C121") (pin "1") (pinfunction "1_1") (pintype "passive"))
      (node (ref "C122") (pin "1") (pinfunction "1_1") (pintype "passive"))
      (node (ref "C123") (pin "1") (pinfunction "1_1") (pintype "passive"))
      (node (ref "C124") (pin "1") (pinfunction "1_1") (pintype "passive"))
      (node (ref "C125") (pin "2") (pinfunction "2_2") (pintype "passive"))
      (node (ref "C126") (pin "2") (pinfunction "2_2") (pintype "passive"))
      (node (ref "C127") (pin "2") (pinfunction "2_2") (pintype "passive"))
      (node (ref "C128") (pin "1") (pinfunction "1_1") (pintype "passive"))
      (node (ref "C129") (pin "1") (pinfunction "1_1") (pintype "passive"))
      (node (ref "C78") (pin "2") (pinfunction "2_2") (pintype "passive"))
      (node (ref "C81") (pin "1") (pinfunction "1_1") (pintype "passive"))
      (node (ref "C82") (pin "1") (pinfunction "1_1") (pintype "passive"))
      (node (ref "C84") (pin "1") (pinfunction "1_1") (pintype "passive"))
      (node (ref "C87") (pin "1") (pinfunction "1_1") (pintype "passive"))
      (node (ref "C89") (pin "2") (pinfunction "2_2") (pintype "passive"))
      (node (ref "C90") (pin "1") (pinfunction "1_1") (pintype "passive"))
      (node (ref "C91") (pin "1") (pinfunction "1_1") (pintype "passive"))
      (node (ref "C92") (pin "1") (pinfunction "1_1") (pintype "passive"))
      (node (ref "C93") (pin "1") (pinfunction "1_1") (pintype "passive"))
      (node (ref "C94") (pin "1") (pinfunction "1_1") (pintype "passive"))
      (node (ref "C95") (pin "1") (pinfunction "1_1") (pintype "passive"))
      (node (ref "C96") (pin "1") (pinfunction "1_1") (pintype "passive"))
      (node (ref "C97") (pin "1") (pinfunction "1_1") (pintype "passive"))
      (node (ref "C98") (pin "1") (pinfunction "1_1") (pintype "passive"))
      (node (ref "C99") (pin "1") (pinfunction "1_1") (pintype "passive"))
      (node (ref "D4") (pin "2") (pinfunction "K_2") (pintype "passive"))
      (node (ref "J12") (pin "2") (pinfunction "-_2") (pintype "input"))
      (node (ref "J14") (pin "7") (pinfunction "7_7") (pintype "passive"))
      (node (ref "J15") (pin "7") (pinfunction "7_7") (pintype "passive"))
      (node (ref "Q2") (pin "2") (pinfunction "E_2") (pintype "passive"))
      (node (ref "Q3") (pin "2") (pinfunction "E_2") (pintype "passive"))
      (node (ref "Q4") (pin "2") (pinfunction "E_2") (pintype "passive"))
      (node (ref "Q5") (pin "2") (pinfunction "E_2") (pintype "passive"))
      (node (ref "R103") (pin "1") (pinfunction "1_1") (pintype "passive"))
      (node (ref "R106") (pin "1") (pinfunction "1_1") (pintype "passive"))
      (node (ref "U17") (pin "1") (pinfunction "NC_1") (pintype "passive"))
      (node (ref "U17") (pin "14") (pinfunction "NC_14") (pintype "passive"))
      (node (ref "U17") (pin "15") (pinfunction "DAP_15") (pintype "power_in"))
      (node (ref "U17") (pin "5") (pinfunction "SGND_5") (pintype "power_in"))
      (node (ref "U17") (pin "6") (pinfunction "RTN_6") (pintype "power_in"))
      (node (ref "U17") (pin "7") (pinfunction "NC_7") (pintype "passive"))
      (node (ref "U17") (pin "8") (pinfunction "NC_8") (pintype "passive"))
      (node (ref "U18") (pin "2") (pinfunction "COM_2") (pintype "power_in"))
      (node (ref "U19") (pin "1") (pinfunction "GND_1") (pintype "power_in"))
      (node (ref "U19") (pin "2") (pinfunction "GND_2") (pintype "power_in"))
    )
    (net (code "14") (name "Net-(C83-Pad1)") (class "Default")
      (node (ref "C83") (pin "1") (pinfunction "1_1") (pintype "passive"))
      (node (ref "C88") (pin "2") (pinfunction "2_2") (pintype "passive"))
      (node (ref "R101") (pin "2") (pinfunction "2_2") (pintype "passive"))
    )
    (net (code "15") (name "Net-(C83-Pad2)") (class "Default")
      (node (ref "C83") (pin "2") (pinfunction "2_2") (pintype "passive"))
      (node (ref "C84") (pin "2") (pinfunction "2_2") (pintype "passive"))
      (node (ref "J11") (pin "2") (pinfunction "2_2") (pintype "passive"))
      (node (ref "L5") (pin "2") (pinfunction "2_2") (pintype "passive"))
      (node (ref "R102") (pin "2") (pinfunction "2_2") (pintype "passive"))
    )
    (net (code "16") (name "Net-(C120-Pad2)") (class "Default")
      (node (ref "C120") (pin "2") (pinfunction "2_2") (pintype "passive"))
      (node (ref "R104") (pin "1") (pinfunction "1_1") (pintype "passive"))
    )
    (net (code "17") (name "Net-(D3-A)") (class "Default")
      (node (ref "D3") (pin "1") (pinfunction "A_1") (pintype "passive"))
      (node (ref "U17") (pin "4") (pinfunction "ISEN_4") (pintype "input"))
    )
    (net (code "18") (name "Net-(D3-K)") (class "Default")
      (node (ref "C80") (pin "2") (pinfunction "2_2") (pintype "passive"))
      (node (ref "D3") (pin "2") (pinfunction "K_2") (pintype "passive"))
      (node (ref "L5") (pin "1") (pinfunction "1_1") (pintype "passive"))
      (node (ref "R101") (pin "1") (pinfunction "1_1") (pintype "passive"))
      (node (ref "U17") (pin "2") (pinfunction "SW_2") (pintype "power_in"))
    )
    (net (code "19") (name "Net-(D4-A)") (class "Default")
      (node (ref "D4") (pin "1") (pinfunction "A_1") (pintype "passive"))
      (node (ref "R107") (pin "1") (pinfunction "1_1") (pintype "passive"))
    )
    (net (code "20") (name "Net-(D5-A)") (class "Default")
      (node (ref "D5") (pin "2") (pinfunction "A_2") (pintype "passive"))
      (node (ref "R108") (pin "1") (pinfunction "1_1") (pintype "passive"))
    )
    (net (code "21") (name "Net-(D5-K)") (class "Default")
      (node (ref "D5") (pin "1") (pinfunction "K_1") (pintype "passive"))
      (node (ref "Q2") (pin "3") (pinfunction "C_3") (pintype "passive"))
    )
    (net (code "22") (name "Net-(D6-A)") (class "Default")
      (node (ref "D6") (pin "1") (pinfunction "A_1") (pintype "passive"))
      (node (ref "R109") (pin "1") (pinfunction "1_1") (pintype "passive"))
    )
    (net (code "23") (name "Net-(D6-K)") (class "Default")
      (node (ref "D6") (pin "2") (pinfunction "K_2") (pintype "passive"))
      (node (ref "Q3") (pin "3") (pinfunction "C_3") (pintype "passive"))
    )
    (net (code "24") (name "Net-(Q2-B)") (class "Default")
      (node (ref "Q2") (pin "1") (pinfunction "B_1") (pintype "passive"))
      (node (ref "Q4") (pin "3") (pinfunction "C_3") (pintype "passive"))
      (node (ref "R110") (pin "1") (pinfunction "1_1") (pintype "passive"))
    )
    (net (code "25") (name "Net-(Q3-B)") (class "Default")
      (node (ref "Q3") (pin "1") (pinfunction "B_1") (pintype "passive"))
      (node (ref "Q5") (pin "3") (pinfunction "C_3") (pintype "passive"))
      (node (ref "R111") (pin "1") (pinfunction "1_1") (pintype "passive"))
    )
    (net (code "26") (name "Net-(Q4-B)") (class "Default")
      (node (ref "Q4") (pin "1") (pinfunction "B_1") (pintype "passive"))
      (node (ref "R112") (pin "2") (pinfunction "2_2") (pintype "passive"))
    )
    (net (code "27") (name "Net-(Q5-B)") (class "Default")
      (node (ref "Q5") (pin "1") (pinfunction "B_1") (pintype "passive"))
      (node (ref "R113") (pin "2") (pinfunction "2_2") (pintype "passive"))
    )
    (net (code "28") (name "Net-(U17-BST)") (class "Default")
      (node (ref "C80") (pin "1") (pinfunction "1_1") (pintype "passive"))
      (node (ref "U17") (pin "3") (pinfunction "BST_3") (pintype "input"))
    )
    (net (code "29") (name "Net-(U17-FB)") (class "Default")
      (node (ref "C88") (pin "1") (pinfunction "1_1") (pintype "passive"))
      (node (ref "R102") (pin "1") (pinfunction "1_1") (pintype "passive"))
      (node (ref "R103") (pin "2") (pinfunction "2_2") (pintype "passive"))
      (node (ref "U17") (pin "9") (pinfunction "FB_9") (pintype "input"))
    )
    (net (code "30") (name "Net-(U17-RON{slash}SD)") (class "Default")
      (node (ref "R100") (pin "1") (pinfunction "1_1") (pintype "passive"))
      (node (ref "U17") (pin "11") (pinfunction "RON/SD_11") (pintype "input"))
    )
    (net (code "31") (name "Net-(U17-SS)") (class "Default")
      (node (ref "C87") (pin "2") (pinfunction "2_2") (pintype "passive"))
      (node (ref "U17") (pin "10") (pinfunction "SS_10") (pintype "input"))
    )
    (net (code "32") (name "Net-(U17-VCC)") (class "Default")
      (node (ref "C78") (pin "1") (pinfunction "1_1") (pintype "passive"))
      (node (ref "U17") (pin "12") (pinfunction "VCC_12") (pintype "power_in"))
    )
    (net (code "33") (name "Net-(U18-NOISE)") (class "Default")
      (node (ref "C118") (pin "2") (pinfunction "2_2") (pintype "passive"))
      (node (ref "U18") (pin "8") (pinfunction "NOISE_8") (pintype "passive"))
    )
    (net (code "34") (name "Net-(U19-VDD)") (class "Default")
      (node (ref "C120") (pin "1") (pinfunction "1_1") (pintype "passive"))
      (node (ref "C121") (pin "2") (pinfunction "2_2") (pintype "passive"))
      (node (ref "C122") (pin "2") (pinfunction "2_2") (pintype "passive"))
      (node (ref "R105") (pin "1") (pinfunction "1_1") (pintype "passive"))
      (node (ref "R106") (pin "2") (pinfunction "2_2") (pintype "passive"))
      (node (ref "U19") (pin "4") (pinfunction "VDD_4") (pintype "power_in"))
    )
    (net (code "35") (name "Net-(U19-~{MR})") (class "Default")
      (node (ref "J13") (pin "2") (pinfunction "2_2") (pintype "passive"))
      (node (ref "U19") (pin "5") (pinfunction "~{MR}_5") (pintype "input"))
    )
    (net (code "36") (name "PVDD") (class "Default")
      (node (ref "C127") (pin "1") (pinfunction "1_1") (pintype "passive"))
      (node (ref "C128") (pin "2") (pinfunction "2_2") (pintype "passive"))
      (node (ref "C129") (pin "2") (pinfunction "2_2") (pintype "passive"))
      (node (ref "C81") (pin "2") (pinfunction "2_2") (pintype "passive"))
      (node (ref "C82") (pin "2") (pinfunction "2_2") (pintype "passive"))
      (node (ref "J12") (pin "1") (pinfunction "+_1") (pintype "input"))
      (node (ref "R100") (pin "2") (pinfunction "2_2") (pintype "passive"))
      (node (ref "R104") (pin "2") (pinfunction "2_2") (pintype "passive"))
      (node (ref "U17") (pin "13") (pinfunction "VIN_13") (pintype "power_in"))
    )
    (net (code "37") (name "VMID") (class "Default")
      (node (ref "J14") (pin "3") (pinfunction "3_3") (pintype "passive"))
      (node (ref "U18") (pin "1") (pinfunction "OUT_1") (pintype "output"))
    )
    (net (code "38") (name "unconnected-(C119-Pad2)") (class "Default")
      (node (ref "C119") (pin "2") (pinfunction "2_2") (pintype "passive"))
    )
    (net (code "39") (name "unconnected-(S2-Pad1)") (class "Default")
      (node (ref "S2") (pin "1") (pinfunction "1_1") (pintype "passive"))
    )
    (net (code "40") (name "unconnected-(S2-Pad2)") (class "Default")
      (node (ref "S2") (pin "2") (pinfunction "2_2") (pintype "passive"))
    )
    (net (code "41") (name "unconnected-(S2-Pad3)") (class "Default")
      (node (ref "S2") (pin "3") (pinfunction "3_3") (pintype "passive"))
    )
    (net (code "42") (name "unconnected-(S2-Pad4)") (class "Default")
      (node (ref "S2") (pin "4") (pinfunction "4_4") (pintype "passive"))
    )
    (net (code "43") (name "unconnected-(U18-N{slash}C-Pad4)") (class "Default")
      (node (ref "U18") (pin "4") (pinfunction "N/C_4") (pintype "passive"))
    )
    (net (code "44") (name "unconnected-(U18-N{slash}C-Pad5)") (class "Default")
      (node (ref "U18") (pin "5") (pinfunction "N/C_5") (pintype "passive"))
    )
    (net (code "45") (name "unconnected-(U18-N{slash}C-Pad6)") (class "Default")
      (node (ref "U18") (pin "6") (pinfunction "N/C_6") (pintype "passive"))
    )
    (net (code "46") (name "unconnected-(U18-N{slash}C-Pad7)") (class "Default")
      (node (ref "U18") (pin "7") (pinfunction "N/C_7") (pintype "passive"))
    )
  )
)
